# Longboard_controller.net
KiCad netlist of a schematic drawn in EAGLE
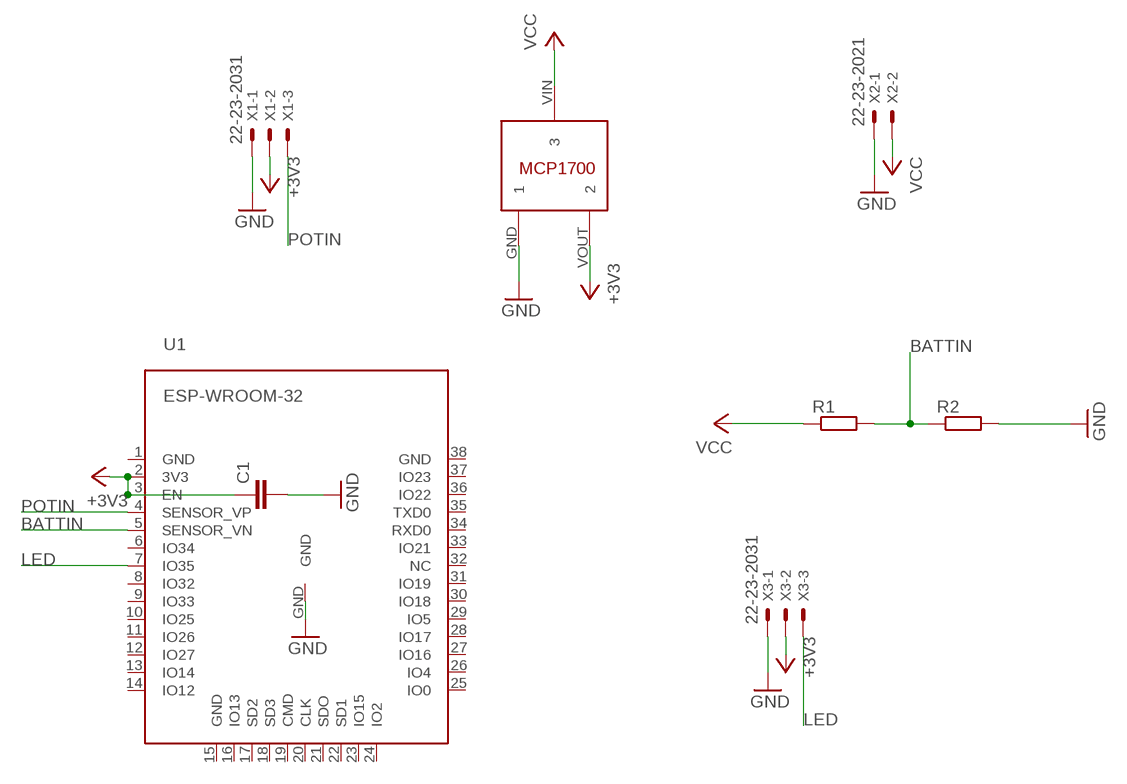
[diagram p0: schematic, sheet 1]

(export (version "E")
  (design (tool "Eeschema 10.0.6"))
  (components
    (comp (ref "C1")
      (value "C-EUC0402")
      (footprint "eagle-import:C0402")
      (libsource (lib "eagle-import") (part "C-EUC0402"))
    )
    (comp (ref "R1")
      (value "R-EU_R0805")
      (footprint "eagle-import:R0805")
      (libsource (lib "eagle-import") (part "R-EU_R0805"))
    )
    (comp (ref "R2")
      (value "R-EU_R0805")
      (footprint "eagle-import:R0805")
      (libsource (lib "eagle-import") (part "R-EU_R0805"))
    )
    (comp (ref "U$1")
      (value "MCP1700T-3302E/TT")
      (footprint "eagle-import:MCP1700T-3302E_TT")
      (libsource (lib "eagle-import") (part "MCP1700T-3302E/TT"))
    )
    (comp (ref "U1")
      (value "ESP-WROOM-32")
      (footprint "eagle-import:ESP-WROOM-32")
      (libsource (lib "eagle-import") (part "ESP-WROOM-32"))
    )
    (comp (ref "X1")
      (value "22-23-2031")
      (footprint "eagle-import:22-23-2031")
      (fields (field (name "MF") "MOLEX"))
      (libsource (lib "eagle-import") (part "22-23-2031"))
    )
    (comp (ref "X2")
      (value "22-23-2021")
      (footprint "eagle-import:22-23-2021")
      (fields (field (name "MF") "MOLEX"))
      (libsource (lib "eagle-import") (part "22-23-2021"))
    )
    (comp (ref "X3")
      (value "22-23-2031")
      (footprint "eagle-import:22-23-2031")
      (fields (field (name "MF") "MOLEX"))
      (libsource (lib "eagle-import") (part "22-23-2031"))
    )
  )
  (nets
    (net (code "1") (name "+3V3") (class "Default")
      (node (ref "C1") (pin "1") (pinfunction "1_1") (pintype "passive"))
      (node (ref "U$1") (pin "VOUT") (pinfunction "2_VOUT") (pintype "bidirectional"))
      (node (ref "U1") (pin "2") (pinfunction "3V3_2") (pintype "bidirectional"))
      (node (ref "U1") (pin "3") (pinfunction "EN_3") (pintype "bidirectional"))
      (node (ref "X1") (pin "2") (pinfunction "S_2") (pintype "passive"))
      (node (ref "X3") (pin "2") (pinfunction "S_2") (pintype "passive"))
    )
    (net (code "2") (name "/BATTIN") (class "Default")
      (node (ref "R1") (pin "2") (pinfunction "2_2") (pintype "passive"))
      (node (ref "R2") (pin "1") (pinfunction "1_1") (pintype "passive"))
      (node (ref "U1") (pin "5") (pinfunction "SENSOR_VN_5") (pintype "bidirectional"))
    )
    (net (code "3") (name "/LED") (class "Default")
      (node (ref "U1") (pin "7") (pinfunction "IO35_7") (pintype "bidirectional"))
      (node (ref "X3") (pin "3") (pinfunction "S_3") (pintype "passive"))
    )
    (net (code "4") (name "/POTIN") (class "Default")
      (node (ref "U1") (pin "4") (pinfunction "SENSOR_VP_4") (pintype "bidirectional"))
      (node (ref "X1") (pin "3") (pinfunction "S_3") (pintype "passive"))
    )
    (net (code "5") (name "GND") (class "Default")
      (node (ref "C1") (pin "2") (pinfunction "2_2") (pintype "passive"))
      (node (ref "R2") (pin "2") (pinfunction "2_2") (pintype "passive"))
      (node (ref "U$1") (pin "GND") (pinfunction "1_GND") (pintype "bidirectional"))
      (node (ref "U1") (pin "GND") (pinfunction "GND_GND") (pintype "bidirectional"))
      (node (ref "X1") (pin "1") (pinfunction "S_1") (pintype "passive"))
      (node (ref "X2") (pin "1") (pinfunction "S_1") (pintype "passive"))
      (node (ref "X3") (pin "1") (pinfunction "S_1") (pintype "passive"))
    )
    (net (code "6") (name "VCC") (class "Default")
      (node (ref "R1") (pin "1") (pinfunction "1_1") (pintype "passive"))
      (node (ref "U$1") (pin "VIN") (pinfunction "3_VIN") (pintype "bidirectional"))
      (node (ref "X2") (pin "2") (pinfunction "S_2") (pintype "passive"))
    )
    (net (code "7") (name "unconnected-(U1-CLK-Pad20)") (class "Default")
      (node (ref "U1") (pin "20") (pinfunction "CLK_20") (pintype "bidirectional"))
    )
    (net (code "8") (name "unconnected-(U1-CMD-Pad19)") (class "Default")
      (node (ref "U1") (pin "19") (pinfunction "CMD_19") (pintype "bidirectional"))
    )
    (net (code "9") (name "unconnected-(U1-GND-Pad1)") (class "Default")
      (node (ref "U1") (pin "1") (pinfunction "GND_1") (pintype "bidirectional"))
    )
    (net (code "10") (name "unconnected-(U1-GND-Pad15)") (class "Default")
      (node (ref "U1") (pin "15") (pinfunction "GND_15") (pintype "bidirectional"))
    )
    (net (code "11") (name "unconnected-(U1-GND-Pad38)") (class "Default")
      (node (ref "U1") (pin "38") (pinfunction "GND_38") (pintype "bidirectional"))
    )
    (net (code "12") (name "unconnected-(U1-IO0-Pad25)") (class "Default")
      (node (ref "U1") (pin "25") (pinfunction "IO0_25") (pintype "bidirectional"))
    )
    (net (code "13") (name "unconnected-(U1-IO2-Pad24)") (class "Default")
      (node (ref "U1") (pin "24") (pinfunction "IO2_24") (pintype "bidirectional"))
    )
    (net (code "14") (name "unconnected-(U1-IO4-Pad26)") (class "Default")
      (node (ref "U1") (pin "26") (pinfunction "IO4_26") (pintype "bidirectional"))
    )
    (net (code "15") (name "unconnected-(U1-IO5-Pad29)") (class "Default")
      (node (ref "U1") (pin "29") (pinfunction "IO5_29") (pintype "bidirectional"))
    )
    (net (code "16") (name "unconnected-(U1-IO12-Pad14)") (class "Default")
      (node (ref "U1") (pin "14") (pinfunction "IO12_14") (pintype "bidirectional"))
    )
    (net (code "17") (name "unconnected-(U1-IO13-Pad16)") (class "Default")
      (node (ref "U1") (pin "16") (pinfunction "IO13_16") (pintype "bidirectional"))
    )
    (net (code "18") (name "unconnected-(U1-IO14-Pad13)") (class "Default")
      (node (ref "U1") (pin "13") (pinfunction "IO14_13") (pintype "bidirectional"))
    )
    (net (code "19") (name "unconnected-(U1-IO15-Pad23)") (class "Default")
      (node (ref "U1") (pin "23") (pinfunction "IO15_23") (pintype "bidirectional"))
    )
    (net (code "20") (name "unconnected-(U1-IO16-Pad27)") (class "Default")
      (node (ref "U1") (pin "27") (pinfunction "IO16_27") (pintype "bidirectional"))
    )
    (net (code "21") (name "unconnected-(U1-IO17-Pad28)") (class "Default")
      (node (ref "U1") (pin "28") (pinfunction "IO17_28") (pintype "bidirectional"))
    )
    (net (code "22") (name "unconnected-(U1-IO18-Pad30)") (class "Default")
      (node (ref "U1") (pin "30") (pinfunction "IO18_30") (pintype "bidirectional"))
    )
    (net (code "23") (name "unconnected-(U1-IO19-Pad31)") (class "Default")
      (node (ref "U1") (pin "31") (pinfunction "IO19_31") (pintype "bidirectional"))
    )
    (net (code "24") (name "unconnected-(U1-IO21-Pad33)") (class "Default")
      (node (ref "U1") (pin "33") (pinfunction "IO21_33") (pintype "bidirectional"))
    )
    (net (code "25") (name "unconnected-(U1-IO22-Pad36)") (class "Default")
      (node (ref "U1") (pin "36") (pinfunction "IO22_36") (pintype "bidirectional"))
    )
    (net (code "26") (name "unconnected-(U1-IO23-Pad37)") (class "Default")
      (node (ref "U1") (pin "37") (pinfunction "IO23_37") (pintype "bidirectional"))
    )
    (net (code "27") (name "unconnected-(U1-IO25-Pad10)") (class "Default")
      (node (ref "U1") (pin "10") (pinfunction "IO25_10") (pintype "bidirectional"))
    )
    (net (code "28") (name "unconnected-(U1-IO26-Pad11)") (class "Default")
      (node (ref "U1") (pin "11") (pinfunction "IO26_11") (pintype "bidirectional"))
    )
    (net (code "29") (name "unconnected-(U1-IO27-Pad12)") (class "Default")
      (node (ref "U1") (pin "12") (pinfunction "IO27_12") (pintype "bidirectional"))
    )
    (net (code "30") (name "unconnected-(U1-IO32-Pad8)") (class "Default")
      (node (ref "U1") (pin "8") (pinfunction "IO32_8") (pintype "bidirectional"))
    )
    (net (code "31") (name "unconnected-(U1-IO33-Pad9)") (class "Default")
      (node (ref "U1") (pin "9") (pinfunction "IO33_9") (pintype "bidirectional"))
    )
    (net (code "32") (name "unconnected-(U1-IO34-Pad6)") (class "Default")
      (node (ref "U1") (pin "6") (pinfunction "IO34_6") (pintype "bidirectional"))
    )
    (net (code "33") (name "unconnected-(U1-NC-Pad32)") (class "Default")
      (node (ref "U1") (pin "32") (pinfunction "NC_32") (pintype "bidirectional"))
    )
    (net (code "34") (name "unconnected-(U1-RXD0-Pad34)") (class "Default")
      (node (ref "U1") (pin "34") (pinfunction "RXD0_34") (pintype "bidirectional"))
    )
    (net (code "35") (name "unconnected-(U1-SD1-Pad22)") (class "Default")
      (node (ref "U1") (pin "22") (pinfunction "SD1_22") (pintype "bidirectional"))
    )
    (net (code "36") (name "unconnected-(U1-SD2-Pad17)") (class "Default")
      (node (ref "U1") (pin "17") (pinfunction "SD2_17") (pintype "bidirectional"))
    )
    (net (code "37") (name "unconnected-(U1-SD3-Pad18)") (class "Default")
      (node (ref "U1") (pin "18") (pinfunction "SD3_18") (pintype "bidirectional"))
    )
    (net (code "38") (name "unconnected-(U1-SDO-Pad21)") (class "Default")
      (node (ref "U1") (pin "21") (pinfunction "SDO_21") (pintype "bidirectional"))
    )
    (net (code "39") (name "unconnected-(U1-TXD0-Pad35)") (class "Default")
      (node (ref "U1") (pin "35") (pinfunction "TXD0_35") (pintype "bidirectional"))
    )
  )
)
